# basestation.net
KiCad netlist of a schematic drawn in EAGLE
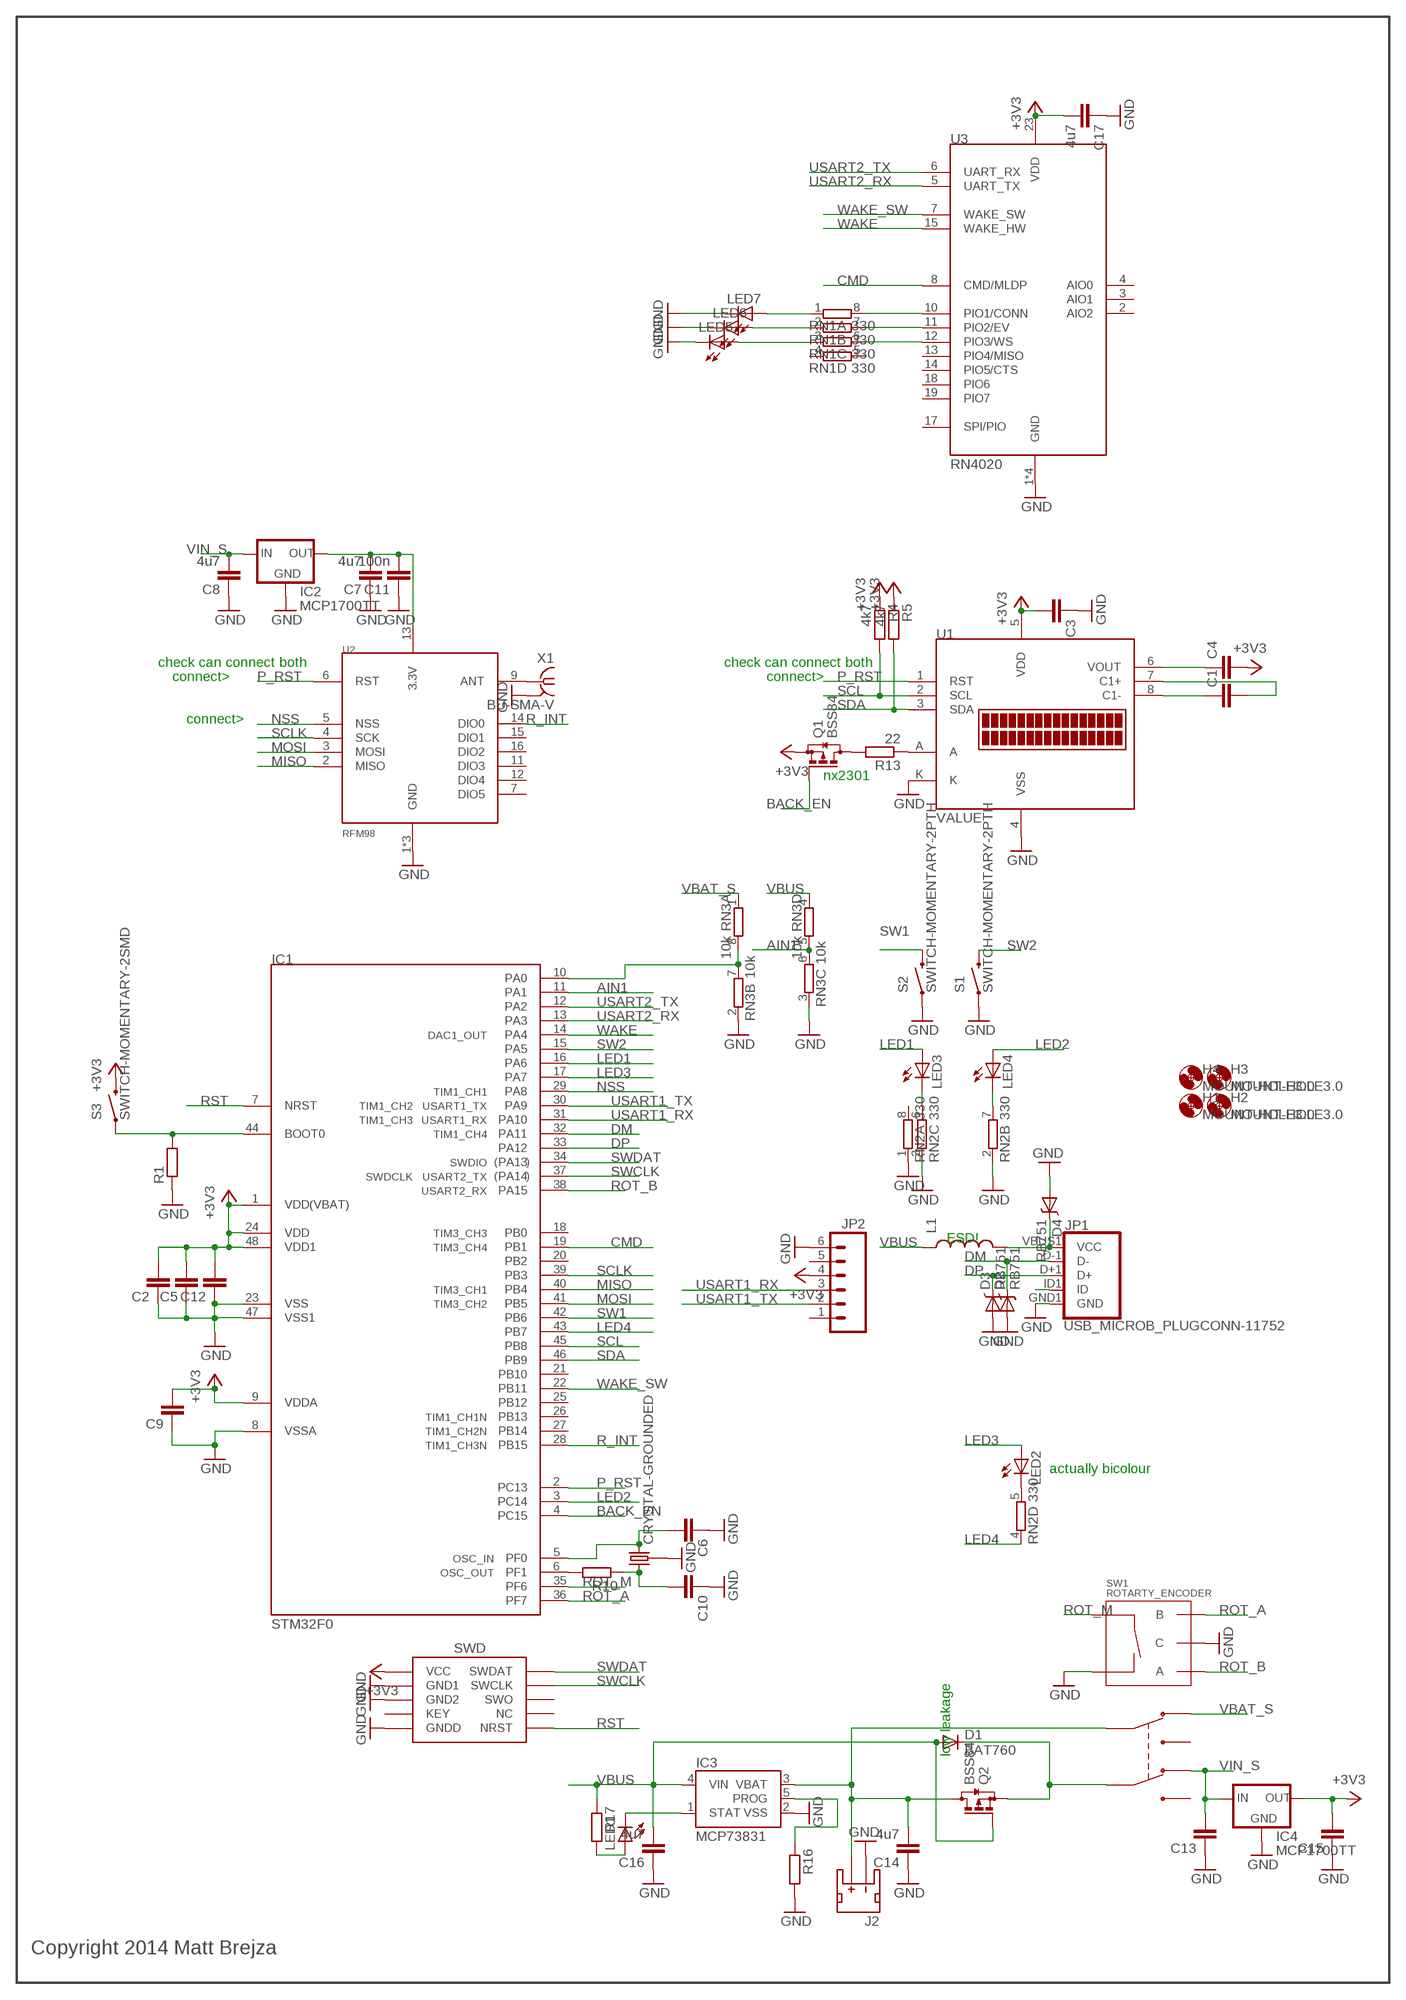
[diagram p0: schematic, sheet 1]

(export (version "E")
  (design (tool "Eeschema 10.0.6"))
  (components
    (comp (ref "C1")
      (value "C-EUC0603")
      (footprint "eagle-import:C0603")
      (libsource (lib "eagle-import") (part "C-EUC0603"))
    )
    (comp (ref "C2")
      (value "C-EUC0603")
      (footprint "eagle-import:C0603")
      (libsource (lib "eagle-import") (part "C-EUC0603"))
    )
    (comp (ref "C3")
      (value "C-EUC0603")
      (footprint "eagle-import:C0603")
      (libsource (lib "eagle-import") (part "C-EUC0603"))
    )
    (comp (ref "C4")
      (value "C-EUC0603")
      (footprint "eagle-import:C0603")
      (libsource (lib "eagle-import") (part "C-EUC0603"))
    )
    (comp (ref "C5")
      (value "C-EUC0603")
      (footprint "eagle-import:C0603")
      (libsource (lib "eagle-import") (part "C-EUC0603"))
    )
    (comp (ref "C6")
      (value "C-EUC0603")
      (footprint "eagle-import:C0603")
      (libsource (lib "eagle-import") (part "C-EUC0603"))
    )
    (comp (ref "C7")
      (value "4u7")
      (footprint "eagle-import:C0603")
      (libsource (lib "eagle-import") (part "C-EUC0603"))
    )
    (comp (ref "C8")
      (value "4u7")
      (footprint "eagle-import:C0603")
      (libsource (lib "eagle-import") (part "C-EUC0603"))
    )
    (comp (ref "C9")
      (value "C-EUC0603")
      (footprint "eagle-import:C0603")
      (libsource (lib "eagle-import") (part "C-EUC0603"))
    )
    (comp (ref "C10")
      (value "C-EUC0603")
      (footprint "eagle-import:C0603")
      (libsource (lib "eagle-import") (part "C-EUC0603"))
    )
    (comp (ref "C11")
      (value "100n")
      (footprint "eagle-import:C0603")
      (libsource (lib "eagle-import") (part "C-EUC0603"))
    )
    (comp (ref "C12")
      (value "C-EUC0603")
      (footprint "eagle-import:C0603")
      (libsource (lib "eagle-import") (part "C-EUC0603"))
    )
    (comp (ref "C13")
      (value "C-EUC0603")
      (footprint "eagle-import:C0603")
      (libsource (lib "eagle-import") (part "C-EUC0603"))
    )
    (comp (ref "C14")
      (value "4u7")
      (footprint "eagle-import:C0603")
      (libsource (lib "eagle-import") (part "C-EUC0603"))
    )
    (comp (ref "C15")
      (value "C-EUC0603")
      (footprint "eagle-import:C0603")
      (libsource (lib "eagle-import") (part "C-EUC0603"))
    )
    (comp (ref "C16")
      (value "4u7")
      (footprint "eagle-import:C0603")
      (libsource (lib "eagle-import") (part "C-EUC0603"))
    )
    (comp (ref "C17")
      (value "4u7")
      (footprint "eagle-import:C0603")
      (libsource (lib "eagle-import") (part "C-EUC0603"))
    )
    (comp (ref "D1")
      (value "BAT760")
      (footprint "eagle-import:SOD323-R")
      (libsource (lib "eagle-import") (part "DIODE-SOD323-R"))
    )
    (comp (ref "D2")
      (value "RB751")
      (footprint "eagle-import:SOD-523")
      (libsource (lib "eagle-import") (part "RB751"))
    )
    (comp (ref "D3")
      (value "RB751")
      (footprint "eagle-import:SOD-523")
      (libsource (lib "eagle-import") (part "RB751"))
    )
    (comp (ref "D4")
      (value "RB751")
      (footprint "eagle-import:SOD-523")
      (libsource (lib "eagle-import") (part "RB751"))
    )
    (comp (ref "H1")
      (value "MOUNT-HOLE3.0")
      (footprint "eagle-import:3,0")
      (libsource (lib "eagle-import") (part "MOUNT-HOLE3.0"))
    )
    (comp (ref "H2")
      (value "MOUNT-HOLE3.0")
      (footprint "eagle-import:3,0")
      (libsource (lib "eagle-import") (part "MOUNT-HOLE3.0"))
    )
    (comp (ref "H3")
      (value "MOUNT-HOLE3.0")
      (footprint "eagle-import:3,0")
      (libsource (lib "eagle-import") (part "MOUNT-HOLE3.0"))
    )
    (comp (ref "H4")
      (value "MOUNT-HOLE3.0")
      (footprint "eagle-import:3,0")
      (libsource (lib "eagle-import") (part "MOUNT-HOLE3.0"))
    )
    (comp (ref "IC1")
      (value "STM32F0")
      (footprint "eagle-import:TQFP48")
      (libsource (lib "eagle-import") (part "STM32F0"))
    )
    (comp (ref "IC2")
      (value "MCP1700TT")
      (footprint "eagle-import:SOT23")
      (libsource (lib "eagle-import") (part "MCP1700TT"))
    )
    (comp (ref "IC3")
      (value "MCP73831")
      (footprint "eagle-import:SOT23-5")
      (libsource (lib "eagle-import") (part "MCP73831"))
    )
    (comp (ref "IC4")
      (value "MCP1700TT")
      (footprint "eagle-import:SOT23")
      (libsource (lib "eagle-import") (part "MCP1700TT"))
    )
    (comp (ref "J1")
      (value "SWD_SHROUD_SMD")
      (footprint "eagle-import:SWD_SMD_SHROUD")
      (libsource (lib "eagle-import") (part "SWD_SHROUD_SMD"))
    )
    (comp (ref "J2")
      (value "JST_2MM_MALE")
      (footprint "eagle-import:JST-2-SMD")
      (libsource (lib "eagle-import") (part "JST_2MM_MALE"))
    )
    (comp (ref "JP1")
      (value "USB_MICROB_PLUGCONN-11752")
      (footprint "eagle-import:USB-B-MICRO-SMD_V03")
      (libsource (lib "eagle-import") (part "USB_MICROB_PLUGCONN-11752"))
    )
    (comp (ref "JP2")
      (value "M06SMD")
      (footprint "eagle-import:1X06-SMD")
      (libsource (lib "eagle-import") (part "M06SMD"))
    )
    (comp (ref "L1")
      (value "INDUCTOR0603")
      (footprint "eagle-import:0603")
      (libsource (lib "eagle-import") (part "INDUCTOR0603"))
    )
    (comp (ref "LED1")
      (value "LEDCHIP-LED0805")
      (footprint "eagle-import:CHIP-LED0805")
      (libsource (lib "eagle-import") (part "LEDCHIP-LED0805"))
    )
    (comp (ref "LED2")
      (value "LED5MM")
      (footprint "eagle-import:LED5MM")
      (libsource (lib "eagle-import") (part "LED5MM"))
    )
    (comp (ref "LED3")
      (value "LED3MM")
      (footprint "eagle-import:LED3MM")
      (libsource (lib "eagle-import") (part "LED3MM"))
    )
    (comp (ref "LED4")
      (value "LED3MM")
      (footprint "eagle-import:LED3MM")
      (libsource (lib "eagle-import") (part "LED3MM"))
    )
    (comp (ref "LED5")
      (value "LEDCHIP-LED0805")
      (footprint "eagle-import:CHIP-LED0805")
      (libsource (lib "eagle-import") (part "LEDCHIP-LED0805"))
    )
    (comp (ref "LED6")
      (value "LEDCHIP-LED0805")
      (footprint "eagle-import:CHIP-LED0805")
      (libsource (lib "eagle-import") (part "LEDCHIP-LED0805"))
    )
    (comp (ref "LED7")
      (value "LEDCHIP-LED0805")
      (footprint "eagle-import:CHIP-LED0805")
      (libsource (lib "eagle-import") (part "LEDCHIP-LED0805"))
    )
    (comp (ref "Q1")
      (value "BSS84")
      (footprint "eagle-import:SOT23")
      (libsource (lib "eagle-import") (part "BSS84"))
    )
    (comp (ref "Q2")
      (value "BSS84")
      (footprint "eagle-import:SOT23")
      (libsource (lib "eagle-import") (part "BSS84"))
    )
    (comp (ref "R1")
      (value "R-EU_R0603")
      (footprint "eagle-import:R0603")
      (libsource (lib "eagle-import") (part "R-EU_R0603"))
    )
    (comp (ref "R4")
      (value "4k7")
      (footprint "eagle-import:R0603")
      (libsource (lib "eagle-import") (part "R-EU_R0603"))
    )
    (comp (ref "R5")
      (value "4k7")
      (footprint "eagle-import:R0603")
      (libsource (lib "eagle-import") (part "R-EU_R0603"))
    )
    (comp (ref "R10")
      (value "R-EU_R0603")
      (footprint "eagle-import:R0603")
      (libsource (lib "eagle-import") (part "R-EU_R0603"))
    )
    (comp (ref "R13")
      (value "22")
      (footprint "eagle-import:R0603")
      (libsource (lib "eagle-import") (part "R-EU_R0603"))
    )
    (comp (ref "R16")
      (value "R-EU_R0603")
      (footprint "eagle-import:R0603")
      (libsource (lib "eagle-import") (part "R-EU_R0603"))
    )
    (comp (ref "R17")
      (value "R-EU_R0603")
      (footprint "eagle-import:R0603")
      (libsource (lib "eagle-import") (part "R-EU_R0603"))
    )
    (comp (ref "RN1")
      (value "330")
      (footprint "eagle-import:EXB38V")
      (libsource (lib "eagle-import") (part "4R-NEXB38V"))
    )
    (comp (ref "RN2")
      (value "330")
      (footprint "eagle-import:EXB38V")
      (libsource (lib "eagle-import") (part "4R-NEXB38V"))
    )
    (comp (ref "RN3")
      (value "10k")
      (footprint "eagle-import:EXB38V")
      (libsource (lib "eagle-import") (part "4R-NEXB38V"))
    )
    (comp (ref "S1")
      (value "SWITCH-MOMENTARY-2PTH")
      (footprint "eagle-import:TACTILE-PTH")
      (libsource (lib "eagle-import") (part "SWITCH-MOMENTARY-2PTH"))
    )
    (comp (ref "S2")
      (value "SWITCH-MOMENTARY-2PTH")
      (footprint "eagle-import:TACTILE-PTH")
      (libsource (lib "eagle-import") (part "SWITCH-MOMENTARY-2PTH"))
    )
    (comp (ref "S3")
      (value "SWITCH-MOMENTARY-2SMD")
      (footprint "eagle-import:TACTILE_SWITCH_SMD")
      (libsource (lib "eagle-import") (part "SWITCH-MOMENTARY-2SMD"))
    )
    (comp (ref "SW1")
      (value "ROTARTY_ENCODER")
      (footprint "eagle-import:ROTARY_ENC_PLAIN")
      (libsource (lib "eagle-import") (part "ROTARTY_ENCODER"))
    )
    (comp (ref "U$1")
      (value "DPDTSLIDE")
      (footprint "eagle-import:DPDTSLIDE")
      (libsource (lib "eagle-import") (part "DPDTSLIDE"))
    )
    (comp (ref "U1")
      (value "NHD-C0216CIZ-FSW")
      (footprint "eagle-import:NHD-C0216CIZ-FSW")
      (libsource (lib "eagle-import") (part "NHD-C0216CIZ-FSW"))
    )
    (comp (ref "U2")
      (value "RFM98")
      (footprint "eagle-import:RFM97")
      (libsource (lib "eagle-import") (part "RFM98"))
    )
    (comp (ref "U3")
      (value "RN4020")
      (footprint "eagle-import:RN4020")
      (libsource (lib "eagle-import") (part "RN4020"))
    )
    (comp (ref "X1")
      (value "BU-SMA-V")
      (footprint "eagle-import:BU-SMA-V")
      (libsource (lib "eagle-import") (part "BU-SMA-V"))
    )
    (comp (ref "X2")
      (value "CRYSTAL-GROUNDED")
      (footprint "eagle-import:CRYSTAL-SMD-5X3")
      (libsource (lib "eagle-import") (part "CRYSTAL-GROUNDED"))
    )
  )
  (nets
    (net (code "1") (name "+3V3") (class "Default")
      (node (ref "C12") (pin "2") (pinfunction "2_2") (pintype "passive"))
      (node (ref "C15") (pin "2") (pinfunction "2_2") (pintype "passive"))
      (node (ref "C17") (pin "2") (pinfunction "2_2") (pintype "passive"))
      (node (ref "C2") (pin "2") (pinfunction "2_2") (pintype "passive"))
      (node (ref "C3") (pin "2") (pinfunction "2_2") (pintype "passive"))
      (node (ref "C4") (pin "2") (pinfunction "2_2") (pintype "passive"))
      (node (ref "C5") (pin "2") (pinfunction "2_2") (pintype "passive"))
      (node (ref "C9") (pin "2") (pinfunction "2_2") (pintype "passive"))
      (node (ref "IC1") (pin "1") (pinfunction "VDD(VBAT)_1") (pintype "power_in"))
      (node (ref "IC1") (pin "24") (pinfunction "VDD_24") (pintype "power_in"))
      (node (ref "IC1") (pin "48") (pinfunction "VDD1_48") (pintype "power_in"))
      (node (ref "IC1") (pin "9") (pinfunction "VDDA_9") (pintype "power_in"))
      (node (ref "IC4") (pin "2") (pinfunction "OUT_2") (pintype "passive"))
      (node (ref "J1") (pin "1") (pinfunction "VCC_1") (pintype "power_in"))
      (node (ref "JP2") (pin "4") (pinfunction "4_4") (pintype "passive"))
      (node (ref "Q1") (pin "2") (pinfunction "S_2") (pintype "passive"))
      (node (ref "R4") (pin "1") (pinfunction "1_1") (pintype "passive"))
      (node (ref "R5") (pin "1") (pinfunction "1_1") (pintype "passive"))
      (node (ref "S3") (pin "3") (pinfunction "2_3") (pintype "passive"))
      (node (ref "U1") (pin "5") (pinfunction "VDD_5") (pintype "power_in"))
      (node (ref "U3") (pin "23") (pinfunction "VDD_23") (pintype "power_in"))
    )
    (net (code "2") (name "/AIN1") (class "Default")
      (node (ref "IC1") (pin "11") (pinfunction "PA1_11") (pintype "bidirectional"))
      (node (ref "RN3") (pin "5") (pinfunction "2_5") (pintype "passive"))
      (node (ref "RN3") (pin "6") (pinfunction "2_6") (pintype "passive"))
    )
    (net (code "3") (name "/BACK_EN") (class "Default")
      (node (ref "IC1") (pin "4") (pinfunction "PC15_4") (pintype "bidirectional"))
      (node (ref "Q1") (pin "1") (pinfunction "G_1") (pintype "passive"))
    )
    (net (code "4") (name "/CMD") (class "Default")
      (node (ref "IC1") (pin "19") (pinfunction "PB1_19") (pintype "bidirectional"))
      (node (ref "U3") (pin "8") (pinfunction "CMD/MLDP_8") (pintype "input"))
    )
    (net (code "5") (name "/DM") (class "Default")
      (node (ref "D2") (pin "C") (pinfunction "C_C") (pintype "passive"))
      (node (ref "IC1") (pin "32") (pinfunction "PA11_32") (pintype "bidirectional"))
      (node (ref "JP1") (pin "D-1") (pinfunction "D-_D-1") (pintype "bidirectional"))
    )
    (net (code "6") (name "/DP") (class "Default")
      (node (ref "D3") (pin "C") (pinfunction "C_C") (pintype "passive"))
      (node (ref "IC1") (pin "33") (pinfunction "PA12_33") (pintype "bidirectional"))
      (node (ref "JP1") (pin "D+1") (pinfunction "D+_D+1") (pintype "bidirectional"))
    )
    (net (code "7") (name "/LED1") (class "Default")
      (node (ref "IC1") (pin "16") (pinfunction "PA6_16") (pintype "bidirectional"))
      (node (ref "LED3") (pin "A") (pinfunction "A_A") (pintype "passive"))
    )
    (net (code "8") (name "/LED2") (class "Default")
      (node (ref "IC1") (pin "3") (pinfunction "PC14_3") (pintype "bidirectional"))
      (node (ref "LED4") (pin "A") (pinfunction "A_A") (pintype "passive"))
    )
    (net (code "9") (name "/LED3") (class "Default")
      (node (ref "IC1") (pin "17") (pinfunction "PA7_17") (pintype "bidirectional"))
      (node (ref "LED2") (pin "A") (pinfunction "A_A") (pintype "passive"))
    )
    (net (code "10") (name "/LED4") (class "Default")
      (node (ref "IC1") (pin "43") (pinfunction "PB7_43") (pintype "bidirectional"))
      (node (ref "RN2") (pin "4") (pinfunction "1_4") (pintype "passive"))
    )
    (net (code "11") (name "/MISO") (class "Default")
      (node (ref "IC1") (pin "40") (pinfunction "PB4_40") (pintype "bidirectional"))
      (node (ref "U2") (pin "2") (pinfunction "MISO_2") (pintype "output"))
    )
    (net (code "12") (name "/MOSI") (class "Default")
      (node (ref "IC1") (pin "41") (pinfunction "PB5_41") (pintype "bidirectional"))
      (node (ref "U2") (pin "3") (pinfunction "MOSI_3") (pintype "input"))
    )
    (net (code "13") (name "/NSS") (class "Default")
      (node (ref "IC1") (pin "29") (pinfunction "PA8_29") (pintype "bidirectional"))
      (node (ref "U2") (pin "5") (pinfunction "NSS_5") (pintype "input"))
    )
    (net (code "14") (name "/P_RST") (class "Default")
      (node (ref "IC1") (pin "2") (pinfunction "PC13_2") (pintype "bidirectional"))
      (node (ref "U1") (pin "1") (pinfunction "RST_1") (pintype "input"))
      (node (ref "U2") (pin "6") (pinfunction "RST_6") (pintype "input"))
    )
    (net (code "15") (name "/ROT_A") (class "Default")
      (node (ref "IC1") (pin "36") (pinfunction "PF7_36") (pintype "bidirectional"))
      (node (ref "SW1") (pin "B") (pinfunction "B_B") (pintype "bidirectional"))
    )
    (net (code "16") (name "/ROT_B") (class "Default")
      (node (ref "IC1") (pin "38") (pinfunction "PA15_38") (pintype "bidirectional"))
      (node (ref "SW1") (pin "A") (pinfunction "A_A") (pintype "bidirectional"))
    )
    (net (code "17") (name "/ROT_M") (class "Default")
      (node (ref "IC1") (pin "35") (pinfunction "PF6_35") (pintype "bidirectional"))
      (node (ref "SW1") (pin "SW+") (pinfunction "SW+_SW+") (pintype "bidirectional"))
    )
    (net (code "18") (name "/RST") (class "Default")
      (node (ref "IC1") (pin "7") (pinfunction "NRST_7") (pintype "input"))
      (node (ref "J1") (pin "10") (pinfunction "NRST_10") (pintype "bidirectional"))
    )
    (net (code "19") (name "/R_INT") (class "Default")
      (node (ref "IC1") (pin "28") (pinfunction "PB15_28") (pintype "bidirectional"))
      (node (ref "U2") (pin "14") (pinfunction "DIO0_14") (pintype "bidirectional"))
    )
    (net (code "20") (name "/SCL") (class "Default")
      (node (ref "IC1") (pin "45") (pinfunction "PB8_45") (pintype "bidirectional"))
      (node (ref "R4") (pin "2") (pinfunction "2_2") (pintype "passive"))
      (node (ref "U1") (pin "2") (pinfunction "SCL_2") (pintype "input"))
    )
    (net (code "21") (name "/SCLK") (class "Default")
      (node (ref "IC1") (pin "39") (pinfunction "PB3_39") (pintype "bidirectional"))
      (node (ref "U2") (pin "4") (pinfunction "SCK_4") (pintype "input"))
    )
    (net (code "22") (name "/SDA") (class "Default")
      (node (ref "IC1") (pin "46") (pinfunction "PB9_46") (pintype "bidirectional"))
      (node (ref "R5") (pin "2") (pinfunction "2_2") (pintype "passive"))
      (node (ref "U1") (pin "3") (pinfunction "SDA_3") (pintype "bidirectional"))
    )
    (net (code "23") (name "/SW1") (class "Default")
      (node (ref "IC1") (pin "42") (pinfunction "PB6_42") (pintype "bidirectional"))
      (node (ref "S2") (pin "3") (pinfunction "2_3") (pintype "passive"))
    )
    (net (code "24") (name "/SW2") (class "Default")
      (node (ref "IC1") (pin "15") (pinfunction "PA5_15") (pintype "bidirectional"))
      (node (ref "S1") (pin "3") (pinfunction "2_3") (pintype "passive"))
    )
    (net (code "25") (name "/SWCLK") (class "Default")
      (node (ref "IC1") (pin "37") (pinfunction "PA14_37") (pintype "bidirectional"))
      (node (ref "J1") (pin "4") (pinfunction "SWCLK_4") (pintype "bidirectional"))
    )
    (net (code "26") (name "/SWDAT") (class "Default")
      (node (ref "IC1") (pin "34") (pinfunction "PA13_34") (pintype "bidirectional"))
      (node (ref "J1") (pin "2") (pinfunction "SWDAT_2") (pintype "bidirectional"))
    )
    (net (code "27") (name "/USART1_RX") (class "Default")
      (node (ref "IC1") (pin "31") (pinfunction "PA10_31") (pintype "bidirectional"))
      (node (ref "JP2") (pin "3") (pinfunction "3_3") (pintype "passive"))
    )
    (net (code "28") (name "/USART1_TX") (class "Default")
      (node (ref "IC1") (pin "30") (pinfunction "PA9_30") (pintype "bidirectional"))
      (node (ref "JP2") (pin "2") (pinfunction "2_2") (pintype "passive"))
    )
    (net (code "29") (name "/USART2_RX") (class "Default")
      (node (ref "IC1") (pin "13") (pinfunction "PA3_13") (pintype "bidirectional"))
      (node (ref "U3") (pin "5") (pinfunction "UART_TX_5") (pintype "output"))
    )
    (net (code "30") (name "/USART2_TX") (class "Default")
      (node (ref "IC1") (pin "12") (pinfunction "PA2_12") (pintype "bidirectional"))
      (node (ref "U3") (pin "6") (pinfunction "UART_RX_6") (pintype "input"))
    )
    (net (code "31") (name "/VBAT_S") (class "Default")
      (node (ref "RN3") (pin "1") (pinfunction "1_1") (pintype "passive"))
      (node (ref "U$1") (pin "1A") (pinfunction "NC0_1A") (pintype "bidirectional"))
    )
    (net (code "32") (name "/VBUS") (class "Default")
      (node (ref "C16") (pin "2") (pinfunction "2_2") (pintype "passive"))
      (node (ref "D1") (pin "A") (pinfunction "A_A") (pintype "passive"))
      (node (ref "IC3") (pin "4") (pinfunction "VIN_4") (pintype "power_in"))
      (node (ref "L1") (pin "1") (pinfunction "1_1") (pintype "passive"))
      (node (ref "Q2") (pin "1") (pinfunction "G_1") (pintype "passive"))
      (node (ref "R17") (pin "1") (pinfunction "1_1") (pintype "passive"))
      (node (ref "RN3") (pin "4") (pinfunction "1_4") (pintype "passive"))
    )
    (net (code "33") (name "/VIN_S") (class "Default")
      (node (ref "C13") (pin "2") (pinfunction "2_2") (pintype "passive"))
      (node (ref "C8") (pin "2") (pinfunction "2_2") (pintype "passive"))
      (node (ref "IC2") (pin "3") (pinfunction "IN_3") (pintype "input"))
      (node (ref "IC4") (pin "3") (pinfunction "IN_3") (pintype "input"))
      (node (ref "U$1") (pin "2A") (pinfunction "NC1_2A") (pintype "bidirectional"))
    )
    (net (code "34") (name "/WAKE") (class "Default")
      (node (ref "IC1") (pin "14") (pinfunction "PA4_14") (pintype "bidirectional"))
      (node (ref "U3") (pin "15") (pinfunction "WAKE_HW_15") (pintype "input"))
    )
    (net (code "35") (name "/WAKE_SW") (class "Default")
      (node (ref "IC1") (pin "22") (pinfunction "PB11_22") (pintype "bidirectional"))
      (node (ref "U3") (pin "7") (pinfunction "WAKE_SW_7") (pintype "input"))
    )
    (net (code "36") (name "GND") (class "Default")
      (node (ref "C10") (pin "1") (pinfunction "1_1") (pintype "passive"))
      (node (ref "C11") (pin "1") (pinfunction "1_1") (pintype "passive"))
      (node (ref "C12") (pin "1") (pinfunction "1_1") (pintype "passive"))
      (node (ref "C13") (pin "1") (pinfunction "1_1") (pintype "passive"))
      (node (ref "C14") (pin "1") (pinfunction "1_1") (pintype "passive"))
      (node (ref "C15") (pin "1") (pinfunction "1_1") (pintype "passive"))
      (node (ref "C16") (pin "1") (pinfunction "1_1") (pintype "passive"))
      (node (ref "C17") (pin "1") (pinfunction "1_1") (pintype "passive"))
      (node (ref "C2") (pin "1") (pinfunction "1_1") (pintype "passive"))
      (node (ref "C3") (pin "1") (pinfunction "1_1") (pintype "passive"))
      (node (ref "C5") (pin "1") (pinfunction "1_1") (pintype "passive"))
      (node (ref "C6") (pin "1") (pinfunction "1_1") (pintype "passive"))
      (node (ref "C7") (pin "1") (pinfunction "1_1") (pintype "passive"))
      (node (ref "C8") (pin "1") (pinfunction "1_1") (pintype "passive"))
      (node (ref "C9") (pin "1") (pinfunction "1_1") (pintype "passive"))
      (node (ref "D2") (pin "A") (pinfunction "A_A") (pintype "passive"))
      (node (ref "D3") (pin "A") (pinfunction "A_A") (pintype "passive"))
      (node (ref "D4") (pin "A") (pinfunction "A_A") (pintype "passive"))
      (node (ref "IC1") (pin "23") (pinfunction "VSS_23") (pintype "power_in"))
      (node (ref "IC1") (pin "47") (pinfunction "VSS1_47") (pintype "power_in"))
      (node (ref "IC1") (pin "8") (pinfunction "VSSA_8") (pintype "power_in"))
      (node (ref "IC2") (pin "1") (pinfunction "GND_1") (pintype "input"))
      (node (ref "IC3") (pin "2") (pinfunction "VSS_2") (pintype "power_in"))
      (node (ref "IC4") (pin "1") (pinfunction "GND_1") (pintype "input"))
      (node (ref "J1") (pin "3") (pinfunction "GND1_3") (pintype "power_in"))
      (node (ref "J1") (pin "5") (pinfunction "GND2_5") (pintype "power_in"))
      (node (ref "J1") (pin "9") (pinfunction "GNDD_9") (pintype "power_in"))
      (node (ref "J2") (pin "1") (pinfunction "-_1") (pintype "bidirectional"))
      (node (ref "JP1") (pin "GND1") (pinfunction "GND_GND1") (pintype "bidirectional"))
      (node (ref "JP2") (pin "6") (pinfunction "6_6") (pintype "passive"))
      (node (ref "LED5") (pin "C") (pinfunction "C_C") (pintype "passive"))
      (node (ref "LED6") (pin "C") (pinfunction "C_C") (pintype "passive"))
      (node (ref "LED7") (pin "C") (pinfunction "C_C") (pintype "passive"))
      (node (ref "R1") (pin "1") (pinfunction "1_1") (pintype "passive"))
      (node (ref "R16") (pin "2") (pinfunction "2_2") (pintype "passive"))
      (node (ref "RN2") (pin "1") (pinfunction "1_1") (pintype "passive"))
      (node (ref "RN2") (pin "2") (pinfunction "1_2") (pintype "passive"))
      (node (ref "RN2") (pin "3") (pinfunction "1_3") (pintype "passive"))
      (node (ref "RN3") (pin "2") (pinfunction "1_2") (pintype "passive"))
      (node (ref "RN3") (pin "3") (pinfunction "1_3") (pintype "passive"))
      (node (ref "S1") (pin "1") (pinfunction "1_1") (pintype "passive"))
      (node (ref "S2") (pin "1") (pinfunction "1_1") (pintype "passive"))
      (node (ref "SW1") (pin "C") (pinfunction "C_C") (pintype "bidirectional"))
      (node (ref "SW1") (pin "SW-") (pinfunction "SW-_SW-") (pintype "bidirectional"))
      (node (ref "U1") (pin "4") (pinfunction "VSS_4") (pintype "power_in"))
      (node (ref "U1") (pin "K") (pinfunction "K_K") (pintype "passive"))
      (node (ref "U2") (pin "1") (pinfunction "GND_1") (pintype "power_in"))
      (node (ref "U2") (pin "10") (pinfunction "GND_10") (pintype "power_in"))
      (node (ref "U2") (pin "8") (pinfunction "GND_8") (pintype "power_in"))
      (node (ref "U3") (pin "1") (pinfunction "GND_1") (pintype "power_in"))
      (node (ref "U3") (pin "16") (pinfunction "GND_16") (pintype "power_in"))
      (node (ref "U3") (pin "24") (pinfunction "GND_24") (pintype "power_in"))
      (node (ref "U3") (pin "9") (pinfunction "GND_9") (pintype "power_in"))
      (node (ref "X1") (pin "2") (pinfunction "2_2") (pintype "passive"))
      (node (ref "X1") (pin "3") (pinfunction "2_3") (pintype "passive"))
      (node (ref "X1") (pin "4") (pinfunction "2_4") (pintype "passive"))
      (node (ref "X1") (pin "5") (pinfunction "2_5") (pintype "passive"))
      (node (ref "X2") (pin "2") (pinfunction "3_2") (pintype "passive"))
      (node (ref "X2") (pin "4") (pinfunction "3_4") (pintype "passive"))
    )
    (net (code "37") (name "Net-(IC1-BOOT0)") (class "Default")
      (node (ref "IC1") (pin "44") (pinfunction "BOOT0_44") (pintype "input"))
      (node (ref "R1") (pin "2") (pinfunction "2_2") (pintype "passive"))
      (node (ref "S3") (pin "1") (pinfunction "1_1") (pintype "passive"))
    )
    (net (code "38") (name "Net-(IC1-PA0)") (class "Default")
      (node (ref "IC1") (pin "10") (pinfunction "PA0_10") (pintype "bidirectional"))
      (node (ref "RN3") (pin "7") (pinfunction "2_7") (pintype "passive"))
      (node (ref "RN3") (pin "8") (pinfunction "2_8") (pintype "passive"))
    )
    (net (code "39") (name "Net-(IC1-PF0)") (class "Default")
      (node (ref "C6") (pin "2") (pinfunction "2_2") (pintype "passive"))
      (node (ref "IC1") (pin "5") (pinfunction "PF0_5") (pintype "bidirectional"))
      (node (ref "X2") (pin "1") (pinfunction "2_1") (pintype "passive"))
    )
    (net (code "40") (name "Net-(IC1-PF1)") (class "Default")
      (node (ref "IC1") (pin "6") (pinfunction "PF1_6") (pintype "bidirectional"))
      (node (ref "R10") (pin "2") (pinfunction "2_2") (pintype "passive"))
    )
    (net (code "41") (name "Net-(IC2-OUT)") (class "Default")
      (node (ref "C11") (pin "2") (pinfunction "2_2") (pintype "passive"))
      (node (ref "C7") (pin "2") (pinfunction "2_2") (pintype "passive"))
      (node (ref "IC2") (pin "2") (pinfunction "OUT_2") (pintype "passive"))
      (node (ref "U2") (pin "13") (pinfunction "3.3V_13") (pintype "power_in"))
    )
    (net (code "42") (name "Net-(IC3-PROG)") (class "Default")
      (node (ref "IC3") (pin "5") (pinfunction "PROG_5") (pintype "input"))
      (node (ref "R16") (pin "1") (pinfunction "1_1") (pintype "passive"))
    )
    (net (code "43") (name "Net-(IC3-STAT)") (class "Default")
      (node (ref "IC3") (pin "1") (pinfunction "STAT_1") (pintype "output"))
      (node (ref "LED1") (pin "C") (pinfunction "C_C") (pintype "passive"))
    )
    (net (code "44") (name "Net-(IC3-VBAT)") (class "Default")
      (node (ref "C14") (pin "2") (pinfunction "2_2") (pintype "passive"))
      (node (ref "IC3") (pin "3") (pinfunction "VBAT_3") (pintype "power_in"))
      (node (ref "J2") (pin "2") (pinfunction "+_2") (pintype "bidirectional"))
      (node (ref "Q2") (pin "3") (pinfunction "D_3") (pintype "passive"))
      (node (ref "U$1") (pin "1X") (pinfunction "COM0_1X") (pintype "bidirectional"))
    )
    (net (code "45") (name "Net-(JP1-VCC)") (class "Default")
      (node (ref "D4") (pin "C") (pinfunction "C_C") (pintype "passive"))
      (node (ref "JP1") (pin "VBUS1") (pinfunction "VCC_VBUS1") (pintype "bidirectional"))
      (node (ref "L1") (pin "2") (pinfunction "2_2") (pintype "passive"))
    )
    (net (code "46") (name "Net-(LED1-PadA)") (class "Default")
      (node (ref "LED1") (pin "A") (pinfunction "A_A") (pintype "passive"))
      (node (ref "R17") (pin "2") (pinfunction "2_2") (pintype "passive"))
    )
    (net (code "47") (name "Net-(LED2-C)") (class "Default")
      (node (ref "LED2") (pin "K") (pinfunction "C_K") (pintype "passive"))
      (node (ref "RN2") (pin "5") (pinfunction "2_5") (pintype "passive"))
    )
    (net (code "48") (name "Net-(LED3-C)") (class "Default")
      (node (ref "LED3") (pin "K") (pinfunction "C_K") (pintype "passive"))
      (node (ref "RN2") (pin "6") (pinfunction "2_6") (pintype "passive"))
    )
    (net (code "49") (name "Net-(LED4-C)") (class "Default")
      (node (ref "LED4") (pin "K") (pinfunction "C_K") (pintype "passive"))
      (node (ref "RN2") (pin "7") (pinfunction "2_7") (pintype "passive"))
    )
    (net (code "50") (name "Net-(LED7-PadA)") (class "Default")
      (node (ref "LED7") (pin "A") (pinfunction "A_A") (pintype "passive"))
      (node (ref "RN1") (pin "1") (pinfunction "1_1") (pintype "passive"))
    )
    (net (code "51") (name "Net-(Q1-D)") (class "Default")
      (node (ref "Q1") (pin "3") (pinfunction "D_3") (pintype "passive"))
      (node (ref "R13") (pin "2") (pinfunction "2_2") (pintype "passive"))
    )
    (net (code "52") (name "Net-(Q2-S)") (class "Default")
      (node (ref "D1") (pin "C") (pinfunction "C_C") (pintype "passive"))
      (node (ref "Q2") (pin "2") (pinfunction "S_2") (pintype "passive"))
      (node (ref "U$1") (pin "2X") (pinfunction "COM1_2X") (pintype "bidirectional"))
    )
    (net (code "53") (name "Net-(R13-Pad1)") (class "Default")
      (node (ref "R13") (pin "1") (pinfunction "1_1") (pintype "passive"))
      (node (ref "U1") (pin "A") (pinfunction "A_A") (pintype "passive"))
    )
    (net (code "54") (name "Net-(RN1A-2)") (class "Default")
      (node (ref "RN1") (pin "8") (pinfunction "2_8") (pintype "passive"))
      (node (ref "U3") (pin "10") (pinfunction "PIO1/CONN_10") (pintype "bidirectional"))
    )
    (net (code "55") (name "Net-(RN1B-1)") (class "Default")
      (node (ref "LED6") (pin "A") (pinfunction "A_A") (pintype "passive"))
      (node (ref "RN1") (pin "2") (pinfunction "1_2") (pintype "passive"))
    )
    (net (code "56") (name "Net-(RN1B-2)") (class "Default")
      (node (ref "RN1") (pin "7") (pinfunction "2_7") (pintype "passive"))
      (node (ref "U3") (pin "11") (pinfunction "PIO2/EV_11") (pintype "bidirectional"))
    )
    (net (code "57") (name "Net-(RN1C-1)") (class "Default")
      (node (ref "LED5") (pin "A") (pinfunction "A_A") (pintype "passive"))
      (node (ref "RN1") (pin "3") (pinfunction "1_3") (pintype "passive"))
    )
    (net (code "58") (name "Net-(RN1C-2)") (class "Default")
      (node (ref "RN1") (pin "6") (pinfunction "2_6") (pintype "passive"))
      (node (ref "U3") (pin "12") (pinfunction "PIO3/WS_12") (pintype "bidirectional"))
    )
    (net (code "59") (name "Net-(U1-C1+)") (class "Default")
      (node (ref "C1") (pin "2") (pinfunction "2_2") (pintype "passive"))
      (node (ref "U1") (pin "7") (pinfunction "C1+_7") (pintype "bidirectional"))
    )
    (net (code "60") (name "Net-(U1-C1-)") (class "Default")
      (node (ref "C1") (pin "1") (pinfunction "1_1") (pintype "passive"))
      (node (ref "U1") (pin "8") (pinfunction "C1-_8") (pintype "bidirectional"))
    )
    (net (code "61") (name "Net-(U1-VOUT)") (class "Default")
      (node (ref "C4") (pin "1") (pinfunction "1_1") (pintype "passive"))
      (node (ref "U1") (pin "6") (pinfunction "VOUT_6") (pintype "bidirectional"))
    )
    (net (code "62") (name "Net-(U2-ANT)") (class "Default")
      (node (ref "U2") (pin "9") (pinfunction "ANT_9") (pintype "bidirectional"))
      (node (ref "X1") (pin "1") (pinfunction "1_1") (pintype "passive"))
    )
    (net (code "63") (name "Net-(X2-1)") (class "Default")
      (node (ref "C10") (pin "2") (pinfunction "2_2") (pintype "passive"))
      (node (ref "R10") (pin "1") (pinfunction "1_1") (pintype "passive"))
      (node (ref "X2") (pin "3") (pinfunction "1_3") (pintype "passive"))
    )
    (net (code "64") (name "unconnected-(IC1-PB0-Pad18)") (class "Default")
      (node (ref "IC1") (pin "18") (pinfunction "PB0_18") (pintype "bidirectional"))
    )
    (net (code "65") (name "unconnected-(IC1-PB2-Pad20)") (class "Default")
      (node (ref "IC1") (pin "20") (pinfunction "PB2_20") (pintype "bidirectional"))
    )
    (net (code "66") (name "unconnected-(IC1-PB10-Pad21)") (class "Default")
      (node (ref "IC1") (pin "21") (pinfunction "PB10_21") (pintype "bidirectional"))
    )
    (net (code "67") (name "unconnected-(IC1-PB12-Pad25)") (class "Default")
      (node (ref "IC1") (pin "25") (pinfunction "PB12_25") (pintype "bidirectional"))
    )
    (net (code "68") (name "unconnected-(IC1-PB13-Pad26)") (class "Default")
      (node (ref "IC1") (pin "26") (pinfunction "PB13_26") (pintype "bidirectional"))
    )
    (net (code "69") (name "unconnected-(IC1-PB14-Pad27)") (class "Default")
      (node (ref "IC1") (pin "27") (pinfunction "PB14_27") (pintype "bidirectional"))
    )
    (net (code "70") (name "unconnected-(J1-KEY-Pad7)") (class "Default")
      (node (ref "J1") (pin "7") (pinfunction "KEY_7") (pintype "bidirectional"))
    )
    (net (code "71") (name "unconnected-(J1-NC-Pad8)") (class "Default")
      (node (ref "J1") (pin "8") (pinfunction "NC_8") (pintype "no_connect"))
    )
    (net (code "72") (name "unconnected-(J1-SWO-Pad6)") (class "Default")
      (node (ref "J1") (pin "6") (pinfunction "SWO_6") (pintype "bidirectional"))
    )
    (net (code "73") (name "unconnected-(J2-PAD1-PadNC1)") (class "Default")
      (node (ref "J2") (pin "NC1") (pinfunction "PAD1_NC1") (pintype "bidirectional"))
    )
    (net (code "74") (name "unconnected-(J2-PAD2-PadNC2)") (class "Default")
      (node (ref "J2") (pin "NC2") (pinfunction "PAD2_NC2") (pintype "bidirectional"))
    )
    (net (code "75") (name "unconnected-(JP1-ID-PadID1)") (class "Default")
      (node (ref "JP1") (pin "ID1") (pinfunction "ID_ID1") (pintype "bidirectional"))
    )
    (net (code "76") (name "unconnected-(JP2-Pad1)") (class "Default")
      (node (ref "JP2") (pin "1") (pinfunction "1_1") (pintype "passive"))
    )
    (net (code "77") (name "unconnected-(JP2-Pad5)") (class "Default")
      (node (ref "JP2") (pin "5") (pinfunction "5_5") (pintype "passive"))
    )
    (net (code "78") (name "unconnected-(RN1D-1-Pad4)") (class "Default")
      (node (ref "RN1") (pin "4") (pinfunction "1_4") (pintype "passive"))
    )
    (net (code "79") (name "unconnected-(RN1D-2-Pad5)") (class "Default")
      (node (ref "RN1") (pin "5") (pinfunction "2_5") (pintype "passive"))
    )
    (net (code "80") (name "unconnected-(RN2A-2-Pad8)") (class "Default")
      (node (ref "RN2") (pin "8") (pinfunction "2_8") (pintype "passive"))
    )
    (net (code "81") (name "unconnected-(U$1-NO0-Pad1B)") (class "Default")
      (node (ref "U$1") (pin "1B") (pinfunction "NO0_1B") (pintype "bidirectional"))
    )
    (net (code "82") (name "unconnected-(U$1-NO1-Pad2B)") (class "Default")
      (node (ref "U$1") (pin "2B") (pinfunction "NO1_2B") (pintype "bidirectional"))
    )
    (net (code "83") (name "unconnected-(U2-DIO1-Pad15)") (class "Default")
      (node (ref "U2") (pin "15") (pinfunction "DIO1_15") (pintype "bidirectional"))
    )
    (net (code "84") (name "unconnected-(U2-DIO2-Pad16)") (class "Default")
      (node (ref "U2") (pin "16") (pinfunction "DIO2_16") (pintype "bidirectional"))
    )
    (net (code "85") (name "unconnected-(U2-DIO3-Pad11)") (class "Default")
      (node (ref "U2") (pin "11") (pinfunction "DIO3_11") (pintype "bidirectional"))
    )
    (net (code "86") (name "unconnected-(U2-DIO4-Pad12)") (class "Default")
      (node (ref "U2") (pin "12") (pinfunction "DIO4_12") (pintype "bidirectional"))
    )
    (net (code "87") (name "unconnected-(U2-DIO5-Pad7)") (class "Default")
      (node (ref "U2") (pin "7") (pinfunction "DIO5_7") (pintype "bidirectional"))
    )
    (net (code "88") (name "unconnected-(U3-AIO0-Pad4)") (class "Default")
      (node (ref "U3") (pin "4") (pinfunction "AIO0_4") (pintype "bidirectional"))
    )
    (net (code "89") (name "unconnected-(U3-AIO1-Pad3)") (class "Default")
      (node (ref "U3") (pin "3") (pinfunction "AIO1_3") (pintype "bidirectional"))
    )
    (net (code "90") (name "unconnected-(U3-AIO2-Pad2)") (class "Default")
      (node (ref "U3") (pin "2") (pinfunction "AIO2_2") (pintype "bidirectional"))
    )
    (net (code "91") (name "unconnected-(U3-PIO4{slash}MISO-Pad13)") (class "Default")
      (node (ref "U3") (pin "13") (pinfunction "PIO4/MISO_13") (pintype "bidirectional"))
    )
    (net (code "92") (name "unconnected-(U3-PIO5{slash}CTS-Pad14)") (class "Default")
      (node (ref "U3") (pin "14") (pinfunction "PIO5/CTS_14") (pintype "bidirectional"))
    )
    (net (code "93") (name "unconnected-(U3-PIO6-Pad18)") (class "Default")
      (node (ref "U3") (pin "18") (pinfunction "PIO6_18") (pintype "bidirectional"))
    )
    (net (code "94") (name "unconnected-(U3-PIO7-Pad19)") (class "Default")
      (node (ref "U3") (pin "19") (pinfunction "PIO7_19") (pintype "bidirectional"))
    )
    (net (code "95") (name "unconnected-(U3-SPI{slash}PIO-Pad17)") (class "Default")
      (node (ref "U3") (pin "17") (pinfunction "SPI/PIO_17") (pintype "input"))
    )
  )
)
